# source_B.net
KiCad netlist of a schematic drawn in Altium Designer
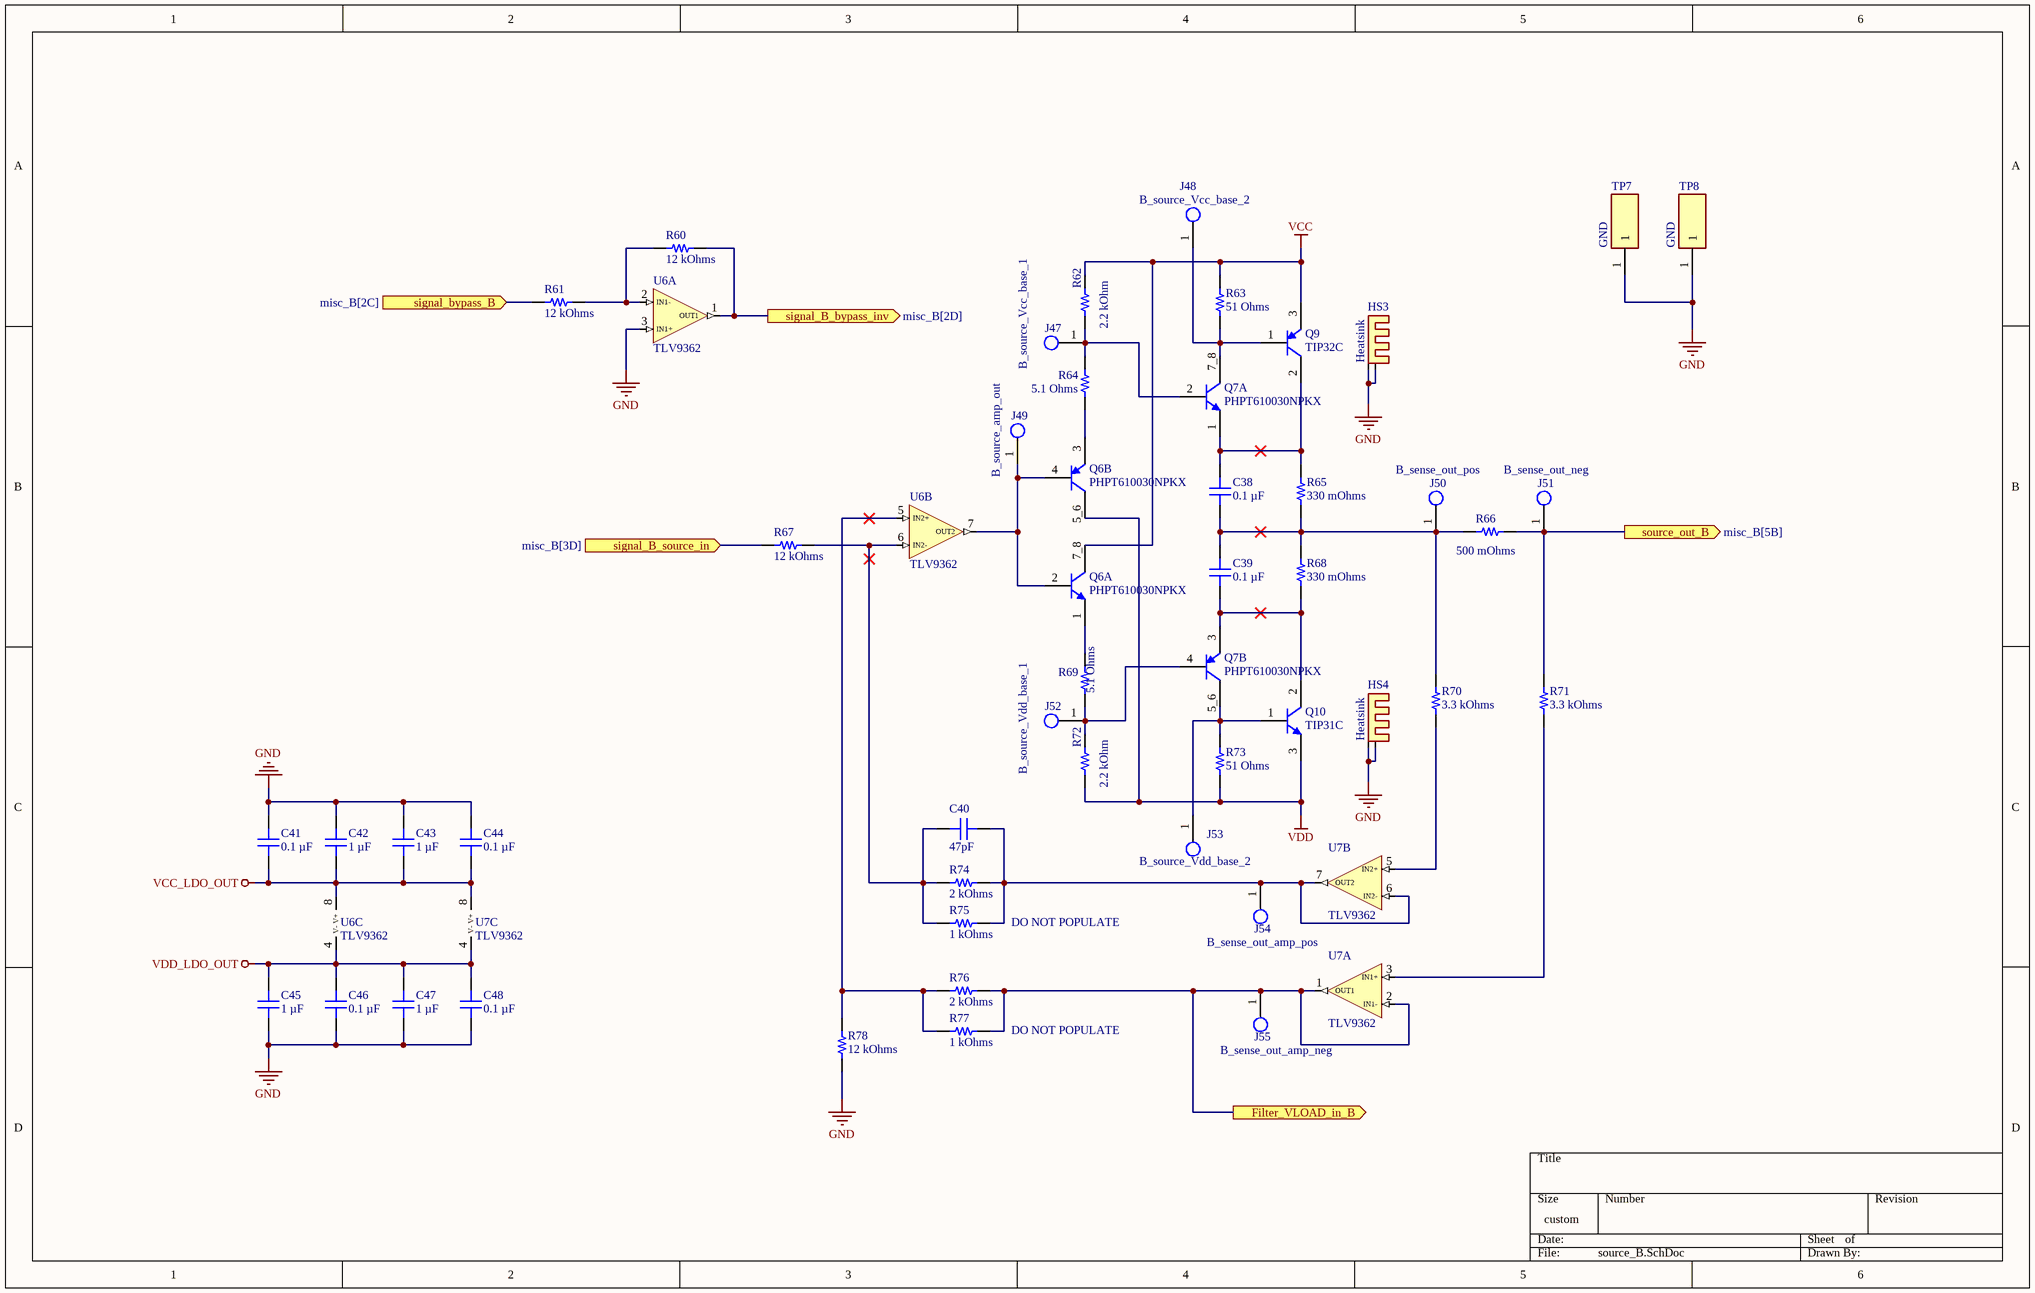
[diagram p0: source_B.SchDoc]

(export (version "E")
  (design (tool "Eeschema 10.0.6"))
  (components
    (comp (ref "C38")
      (value "0.1 µF")
      (footprint "CAP 1206_3216 - 0.8MM")
      (description "CAP CER 0.1UF 50V X7R 1206")
      (fields
        (field (name "PART NUMBER") "885012208087")
        (field (name "CAPACITANCE") "0.1 µF")
        (field (name "MANUFACTURER") "Würth Elektronik")
      )
      (libsource (lib "Celestial Altium Library - altium_library") (part "Capacitor"))
    )
    (comp (ref "C39")
      (value "0.1 µF")
      (footprint "CAP 1206_3216 - 0.8MM")
      (description "CAP CER 0.1UF 50V X7R 1206")
      (fields
        (field (name "PART NUMBER") "885012208087")
        (field (name "CAPACITANCE") "0.1 µF")
        (field (name "MANUFACTURER") "Würth Elektronik")
      )
      (libsource (lib "Celestial Altium Library - altium_library") (part "Capacitor"))
    )
    (comp (ref "C40")
      (value "47pF")
      (footprint "CAP 1206_3216 - 1.8MM")
      (description "CAP CER 47PF 1KV C0G/NP0 1206")
      (fields
        (field (name "PART NUMBER") "1206AA470KAT1A")
        (field (name "CAPACITANCE") "47pF")
        (field (name "MANUFACTURER") "AVX Corporation")
      )
      (libsource (lib "Celestial Altium Library - altium_library") (part "Capacitor"))
    )
    (comp (ref "C41")
      (value "0.1 µF")
      (footprint "CAP 1206_3216 - 0.8MM")
      (description "CAP CER 0.1UF 50V X7R 1206")
      (fields
        (field (name "PART NUMBER") "885012208087")
        (field (name "CAPACITANCE") "0.1 µF")
        (field (name "MANUFACTURER") "Würth Elektronik")
      )
      (libsource (lib "Celestial Altium Library - altium_library") (part "Capacitor"))
    )
    (comp (ref "C42")
      (value "1 µF")
      (footprint "CAP 1206_3216 - 0.8MM")
      (description "CAP CER 1UF 50V X7R 1206")
      (fields
        (field (name "PART NUMBER") "885012208093")
        (field (name "CAPACITANCE") "1 µF")
        (field (name "MANUFACTURER") "Würth Elektronik")
      )
      (libsource (lib "Celestial Altium Library - altium_library") (part "Capacitor"))
    )
    (comp (ref "C43")
      (value "1 µF")
      (footprint "CAP 1206_3216 - 0.8MM")
      (description "CAP CER 1UF 50V X7R 1206")
      (fields
        (field (name "PART NUMBER") "885012208093")
        (field (name "CAPACITANCE") "1 µF")
        (field (name "MANUFACTURER") "Würth Elektronik")
      )
      (libsource (lib "Celestial Altium Library - altium_library") (part "Capacitor"))
    )
    (comp (ref "C44")
      (value "0.1 µF")
      (footprint "CAP 1206_3216 - 0.8MM")
      (description "CAP CER 0.1UF 50V X7R 1206")
      (fields
        (field (name "PART NUMBER") "885012208087")
        (field (name "CAPACITANCE") "0.1 µF")
        (field (name "MANUFACTURER") "Würth Elektronik")
      )
      (libsource (lib "Celestial Altium Library - altium_library") (part "Capacitor"))
    )
    (comp (ref "C45")
      (value "1 µF")
      (footprint "CAP 1206_3216 - 0.8MM")
      (description "CAP CER 1UF 50V X7R 1206")
      (fields
        (field (name "PART NUMBER") "885012208093")
        (field (name "CAPACITANCE") "1 µF")
        (field (name "MANUFACTURER") "Würth Elektronik")
      )
      (libsource (lib "Celestial Altium Library - altium_library") (part "Capacitor"))
    )
    (comp (ref "C46")
      (value "0.1 µF")
      (footprint "CAP 1206_3216 - 0.8MM")
      (description "CAP CER 0.1UF 50V X7R 1206")
      (fields
        (field (name "PART NUMBER") "885012208087")
        (field (name "CAPACITANCE") "0.1 µF")
        (field (name "MANUFACTURER") "Würth Elektronik")
      )
      (libsource (lib "Celestial Altium Library - altium_library") (part "Capacitor"))
    )
    (comp (ref "C47")
      (value "1 µF")
      (footprint "CAP 1206_3216 - 0.8MM")
      (description "CAP CER 1UF 50V X7R 1206")
      (fields
        (field (name "PART NUMBER") "885012208093")
        (field (name "CAPACITANCE") "1 µF")
        (field (name "MANUFACTURER") "Würth Elektronik")
      )
      (libsource (lib "Celestial Altium Library - altium_library") (part "Capacitor"))
    )
    (comp (ref "C48")
      (value "0.1 µF")
      (footprint "CAP 1206_3216 - 0.8MM")
      (description "CAP CER 0.1UF 50V X7R 1206")
      (fields
        (field (name "PART NUMBER") "885012208087")
        (field (name "CAPACITANCE") "0.1 µF")
        (field (name "MANUFACTURER") "Würth Elektronik")
      )
      (libsource (lib "Celestial Altium Library - altium_library") (part "Capacitor"))
    )
    (comp (ref "HS3")
      (value "Heatsink")
      (footprint "593002B03400G")
      (description "593002B03400G Heatsink TO220 13.4 C/W")
      (fields
        (field (name "MANUFACTURER_PART_NUMBER") "593002B03400G")
        (field (name "MOUSER PART NUMBER") "532-593002B03400G")
      )
      (libsource (lib "za_koncar") (part "593002B03400G"))
    )
    (comp (ref "HS4")
      (value "Heatsink")
      (footprint "593002B03400G")
      (description "593002B03400G Heatsink TO220 13.4 C/W")
      (fields
        (field (name "MANUFACTURER_PART_NUMBER") "593002B03400G")
        (field (name "MOUSER PART NUMBER") "532-593002B03400G")
      )
      (libsource (lib "za_koncar") (part "593002B03400G"))
    )
    (comp (ref "J47")
      (value "B_source_Vcc_base_1")
      (footprint "FP-5001-MFG")
      (description "PC TEST POINT MINIATURE BLACK")
      (libsource (lib "za_koncar") (part "5001"))
    )
    (comp (ref "J48")
      (value "B_source_Vcc_base_2")
      (footprint "FP-5001-MFG")
      (description "PC TEST POINT MINIATURE BLACK")
      (libsource (lib "za_koncar") (part "5001"))
    )
    (comp (ref "J49")
      (value "B_source_amp_out")
      (footprint "FP-5001-MFG")
      (description "PC TEST POINT MINIATURE BLACK")
      (libsource (lib "za_koncar") (part "5001"))
    )
    (comp (ref "J50")
      (value "B_sense_out_pos")
      (footprint "FP-5001-MFG")
      (description "PC TEST POINT MINIATURE BLACK")
      (libsource (lib "za_koncar") (part "5001"))
    )
    (comp (ref "J51")
      (value "B_sense_out_neg")
      (footprint "FP-5001-MFG")
      (description "PC TEST POINT MINIATURE BLACK")
      (libsource (lib "za_koncar") (part "5001"))
    )
    (comp (ref "J52")
      (value "B_source_Vdd_base_1")
      (footprint "FP-5001-MFG")
      (description "PC TEST POINT MINIATURE BLACK")
      (libsource (lib "za_koncar") (part "5001"))
    )
    (comp (ref "J53")
      (value "B_source_Vdd_base_2")
      (footprint "FP-5001-MFG")
      (description "PC TEST POINT MINIATURE BLACK")
      (libsource (lib "za_koncar") (part "5001"))
    )
    (comp (ref "J54")
      (value "B_sense_out_amp_pos")
      (footprint "FP-5001-MFG")
      (description "PC TEST POINT MINIATURE BLACK")
      (libsource (lib "za_koncar") (part "5001"))
    )
    (comp (ref "J55")
      (value "B_sense_out_amp_neg")
      (footprint "FP-5001-MFG")
      (description "PC TEST POINT MINIATURE BLACK")
      (libsource (lib "za_koncar") (part "5001"))
    )
    (comp (ref "Q6")
      (value "PHPT610030NPKX")
      (footprint "TRANS_BUK9K18-40E,115")
      (libsource (lib "za_koncar") (part "PHPT610030NPKX"))
    )
    (comp (ref "Q7")
      (value "PHPT610030NPKX")
      (footprint "TRANS_BUK9K18-40E,115")
      (libsource (lib "za_koncar") (part "PHPT610030NPKX"))
    )
    (comp (ref "Q9")
      (value "TIP32C")
      (footprint "ONSC-TO-220-3-221A-09")
      (description "Complementary Silicon Plastic Power Transistor, 3-Pin TO-220, Tube")
      (fields (field (name "MANUFACTURER") "On Semiconductor"))
      (libsource (lib "ON Semi General Purpose Transistors") (part "TIP32C"))
    )
    (comp (ref "Q10")
      (value "TIP31C")
      (footprint "ONSC-TO-220-3-221A-09")
      (description "Complementary Silicon Plastic Power Transistor, 3-Pin TO-220, Tube")
      (fields (field (name "MANUFACTURER") "On Semiconductor"))
      (libsource (lib "ON Semi General Purpose Transistors") (part "TIP31C"))
    )
    (comp (ref "R60")
      (value "12 kOhms")
      (footprint "RES 1206_3216")
      (description "RES SMD 12K OHM 0.1% 1/4W 1206")
      (fields
        (field (name "PART NUMBER") "ERA-8AEB123V")
        (field (name "MANUFACTURER") "Panasonic Electronic Components")
      )
      (libsource (lib "Celestial Altium Library - altium_library") (part "Resistor"))
    )
    (comp (ref "R61")
      (value "12 kOhms")
      (footprint "RES 1206_3216")
      (description "RES SMD 12K OHM 0.1% 1/4W 1206")
      (fields
        (field (name "PART NUMBER") "ERA-8AEB123V")
        (field (name "MANUFACTURER") "Panasonic Electronic Components")
      )
      (libsource (lib "Celestial Altium Library - altium_library") (part "Resistor"))
    )
    (comp (ref "R62")
      (value "2.2 kOhm")
      (footprint "za_koncar:RESC3116X65N")
      (description "Resistor")
      (fields
        (field (name "MANUFACTURER_PART_NUMBER") "RT1206FRE072K2L")
        (field (name "MOUSER PART NUMBER") "603-RT1206FRE072K2L")
      )
      (libsource (lib "za_koncar") (part "RT1206FRE072K2L"))
    )
    (comp (ref "R63")
      (value "51 Ohms")
      (footprint "RES 1206_3216")
      (description "RES SMD 51 OHM 5% 1/4W 1206")
      (fields
        (field (name "PART NUMBER") "ERJ-8GEYJ510V")
        (field (name "MANUFACTURER") "Panasonic Electronic Components")
      )
      (libsource (lib "Celestial Altium Library - altium_library") (part "Resistor"))
    )
    (comp (ref "R64")
      (value "5.1 Ohms")
      (footprint "RES 1206_3216")
      (description "RES SMD 5.1 OHM 5% 1/4W 1206")
      (fields
        (field (name "PART NUMBER") "ERJ-8GEYJ5R1V")
        (field (name "MANUFACTURER") "Panasonic Electronic Components")
      )
      (libsource (lib "Celestial Altium Library - altium_library") (part "Resistor"))
    )
    (comp (ref "R65")
      (value "330 mOhms")
      (footprint "STACKPOLE CSR2512")
      (description "RES 0.33 OHM 1% 2W 2512")
      (fields
        (field (name "PART NUMBER") "CSRN2512FKR330")
        (field (name "MANUFACTURER") "Stackpole Electronics Inc")
      )
      (libsource (lib "Celestial Altium Library - altium_library") (part "Resistor"))
    )
    (comp (ref "R66")
      (value "500 mOhms")
      (footprint "STACKPOLE CSR2512")
      (description "RES 0.5 OHM 1% 2W 2512")
      (fields
        (field (name "PART NUMBER") "CSRN2512FKR500")
        (field (name "MANUFACTURER") "Stackpole Electronics Inc")
      )
      (libsource (lib "Celestial Altium Library - altium_library") (part "Resistor"))
    )
    (comp (ref "R67")
      (value "12 kOhms")
      (footprint "RES 1206_3216")
      (description "RES SMD 12K OHM 0.1% 1/4W 1206")
      (fields
        (field (name "PART NUMBER") "ERA-8AEB123V")
        (field (name "MANUFACTURER") "Panasonic Electronic Components")
      )
      (libsource (lib "Celestial Altium Library - altium_library") (part "Resistor"))
    )
    (comp (ref "R68")
      (value "330 mOhms")
      (footprint "STACKPOLE CSR2512")
      (description "RES 0.33 OHM 1% 2W 2512")
      (fields
        (field (name "PART NUMBER") "CSRN2512FKR330")
        (field (name "MANUFACTURER") "Stackpole Electronics Inc")
      )
      (libsource (lib "Celestial Altium Library - altium_library") (part "Resistor"))
    )
    (comp (ref "R69")
      (value "5.1 Ohms")
      (footprint "RES 1206_3216")
      (description "RES SMD 5.1 OHM 5% 1/4W 1206")
      (fields
        (field (name "PART NUMBER") "ERJ-8GEYJ5R1V")
        (field (name "MANUFACTURER") "Panasonic Electronic Components")
      )
      (libsource (lib "Celestial Altium Library - altium_library") (part "Resistor"))
    )
    (comp (ref "R70")
      (value "3.3 kOhms")
      (footprint "YAGEO RES 1206_3216")
      (description "RES SMD 3.3K OHM 1% 1/4W 1206")
      (fields (field (name "PART NUMBER") "RT1206FRE073K3L") (field (name "MANUFACTURER") "Yageo"))
      (libsource (lib "Celestial Altium Library - altium_library") (part "Resistor"))
    )
    (comp (ref "R71")
      (value "3.3 kOhms")
      (footprint "YAGEO RES 1206_3216")
      (description "RES SMD 3.3K OHM 1% 1/4W 1206")
      (fields (field (name "PART NUMBER") "RT1206FRE073K3L") (field (name "MANUFACTURER") "Yageo"))
      (libsource (lib "Celestial Altium Library - altium_library") (part "Resistor"))
    )
    (comp (ref "R72")
      (value "2.2 kOhm")
      (footprint "za_koncar:RESC3116X65N")
      (description "Resistor")
      (fields
        (field (name "MANUFACTURER_PART_NUMBER") "RT1206FRE072K2L")
        (field (name "MOUSER PART NUMBER") "603-RT1206FRE072K2L")
      )
      (libsource (lib "za_koncar") (part "RT1206FRE072K2L"))
    )
    (comp (ref "R73")
      (value "51 Ohms")
      (footprint "RES 1206_3216")
      (description "RES SMD 51 OHM 5% 1/4W 1206")
      (fields
        (field (name "PART NUMBER") "ERJ-8GEYJ510V")
        (field (name "MANUFACTURER") "Panasonic Electronic Components")
      )
      (libsource (lib "Celestial Altium Library - altium_library") (part "Resistor"))
    )
    (comp (ref "R74")
      (value "2 kOhms")
      (footprint "RES 1206_3216")
      (description "RES SMD 2K OHM 0.1% 1/4W 1206")
      (fields
        (field (name "PART NUMBER") "ERA-8AEB202V")
        (field (name "MANUFACTURER") "Panasonic Electronic Components")
      )
      (libsource (lib "Celestial Altium Library - altium_library") (part "Resistor"))
    )
    (comp (ref "R75")
      (value "1 kOhms")
      (footprint "RES 1206_3216")
      (description "RES SMD 1K OHM 0.1% 1/4W 1206")
      (fields
        (field (name "PART NUMBER") "ERA-8AEB102V")
        (field (name "MANUFACTURER") "Panasonic Electronic Components")
      )
      (libsource (lib "Celestial Altium Library - altium_library") (part "Resistor"))
    )
    (comp (ref "R76")
      (value "2 kOhms")
      (footprint "RES 1206_3216")
      (description "RES SMD 2K OHM 0.1% 1/4W 1206")
      (fields
        (field (name "PART NUMBER") "ERA-8AEB202V")
        (field (name "MANUFACTURER") "Panasonic Electronic Components")
      )
      (libsource (lib "Celestial Altium Library - altium_library") (part "Resistor"))
    )
    (comp (ref "R77")
      (value "1 kOhms")
      (footprint "RES 1206_3216")
      (description "RES SMD 1K OHM 0.1% 1/4W 1206")
      (fields
        (field (name "PART NUMBER") "ERA-8AEB102V")
        (field (name "MANUFACTURER") "Panasonic Electronic Components")
      )
      (libsource (lib "Celestial Altium Library - altium_library") (part "Resistor"))
    )
    (comp (ref "R78")
      (value "12 kOhms")
      (footprint "RES 1206_3216")
      (description "RES SMD 12K OHM 0.1% 1/4W 1206")
      (fields
        (field (name "PART NUMBER") "ERA-8AEB123V")
        (field (name "MANUFACTURER") "Panasonic Electronic Components")
      )
      (libsource (lib "Celestial Altium Library - altium_library") (part "Resistor"))
    )
    (comp (ref "TP7")
      (value "GND")
      (footprint "za_koncar:S175146R")
      (description "Test Point")
      (fields
        (field (name "MANUFACTURER_PART_NUMBER") "S1751-46R")
        (field (name "MOUSER PART NUMBER") "855-S1751-46R")
      )
      (libsource (lib "za_koncar") (part "S1751-46R"))
    )
    (comp (ref "TP8")
      (value "GND")
      (footprint "za_koncar:S175146R")
      (description "Test Point")
      (fields
        (field (name "MANUFACTURER_PART_NUMBER") "S1751-46R")
        (field (name "MOUSER PART NUMBER") "855-S1751-46R")
      )
      (libsource (lib "za_koncar") (part "S1751-46R"))
    )
    (comp (ref "U6")
      (value "TLV9362")
      (footprint "SOIC8-127P600X175-8N")
      (description "TLV936x 10-MHz, 40-V, RRO, Operational Amplifie")
      (libsource (lib "za_koncar") (part "TLV9362"))
    )
    (comp (ref "U7")
      (value "TLV9362")
      (footprint "SOIC8-127P600X175-8N")
      (description "TLV936x 10-MHz, 40-V, RRO, Operational Amplifie")
      (libsource (lib "za_koncar") (part "TLV9362"))
    )
  )
  (nets
    (net (code "1") (name "/Filter_VLOAD_in_B") (class "Default")
      (node (ref "J55") (pin "1") (pinfunction "1_1") (pintype "passive"))
      (node (ref "R76") (pin "2") (pinfunction "2_2") (pintype "passive"))
      (node (ref "R77") (pin "2") (pinfunction "2_2") (pintype "passive"))
      (node (ref "U7") (pin "1") (pinfunction "OUT1_1") (pintype "output"))
      (node (ref "U7") (pin "2") (pinfunction "IN1-_2") (pintype "input"))
    )
    (net (code "2") (name "/signal_B_bypass_inv") (class "Default")
      (node (ref "R60") (pin "2") (pinfunction "2_2") (pintype "passive"))
      (node (ref "U6") (pin "1") (pinfunction "OUT1_1") (pintype "output"))
    )
    (net (code "3") (name "/signal_B_source_in") (class "Default")
      (node (ref "R67") (pin "2") (pinfunction "2_2") (pintype "passive"))
    )
    (net (code "4") (name "/signal_bypass_B") (class "Default")
      (node (ref "R61") (pin "2") (pinfunction "2_2") (pintype "passive"))
    )
    (net (code "5") (name "/source_out_B") (class "Default")
      (node (ref "J51") (pin "1") (pinfunction "1_1") (pintype "passive"))
      (node (ref "R66") (pin "1") (pinfunction "1_1") (pintype "passive"))
      (node (ref "R71") (pin "1") (pinfunction "1_1") (pintype "passive"))
    )
    (net (code "6") (name "GND") (class "Default")
      (node (ref "C41") (pin "1") (pinfunction "1_1") (pintype "passive"))
      (node (ref "C42") (pin "1") (pinfunction "1_1") (pintype "passive"))
      (node (ref "C43") (pin "2") (pinfunction "2_2") (pintype "passive"))
      (node (ref "C44") (pin "2") (pinfunction "2_2") (pintype "passive"))
      (node (ref "C45") (pin "2") (pinfunction "2_2") (pintype "passive"))
      (node (ref "C46") (pin "2") (pinfunction "2_2") (pintype "passive"))
      (node (ref "C47") (pin "2") (pinfunction "2_2") (pintype "passive"))
      (node (ref "C48") (pin "2") (pinfunction "2_2") (pintype "passive"))
      (node (ref "HS3") (pin "1") (pinfunction "1_1") (pintype "passive"))
      (node (ref "HS3") (pin "2") (pinfunction "2_2") (pintype "passive"))
      (node (ref "HS4") (pin "1") (pinfunction "1_1") (pintype "passive"))
      (node (ref "HS4") (pin "2") (pinfunction "2_2") (pintype "passive"))
      (node (ref "R78") (pin "1") (pinfunction "1_1") (pintype "passive"))
      (node (ref "TP7") (pin "1") (pinfunction "1_1") (pintype "passive"))
      (node (ref "TP8") (pin "1") (pinfunction "1_1") (pintype "passive"))
      (node (ref "U6") (pin "3") (pinfunction "IN1+_3") (pintype "input"))
    )
    (net (code "7") (name "Net-(C38-Pad1)") (class "Default")
      (node (ref "C38") (pin "1") (pinfunction "1_1") (pintype "passive"))
      (node (ref "C39") (pin "2") (pinfunction "2_2") (pintype "passive"))
      (node (ref "J50") (pin "1") (pinfunction "1_1") (pintype "passive"))
      (node (ref "R65") (pin "1") (pinfunction "1_1") (pintype "passive"))
      (node (ref "R66") (pin "2") (pinfunction "2_2") (pintype "passive"))
      (node (ref "R68") (pin "2") (pinfunction "2_2") (pintype "passive"))
      (node (ref "R70") (pin "1") (pinfunction "1_1") (pintype "passive"))
    )
    (net (code "8") (name "Net-(Q6A-B1)") (class "Default")
      (node (ref "J49") (pin "1") (pinfunction "1_1") (pintype "passive"))
      (node (ref "Q6") (pin "2") (pinfunction "B1_2") (pintype "passive"))
      (node (ref "Q6") (pin "4") (pinfunction "B2_4") (pintype "passive"))
      (node (ref "U6") (pin "7") (pinfunction "OUT2_7") (pintype "output"))
    )
    (net (code "9") (name "Net-(Q6A-E1)") (class "Default")
      (node (ref "Q6") (pin "1") (pinfunction "E1_1") (pintype "passive"))
      (node (ref "R69") (pin "2") (pinfunction "2_2") (pintype "passive"))
    )
    (net (code "10") (name "Net-(Q6B-E2)") (class "Default")
      (node (ref "Q6") (pin "3") (pinfunction "E2_3") (pintype "passive"))
      (node (ref "R64") (pin "1") (pinfunction "1_1") (pintype "passive"))
    )
    (net (code "11") (name "Net-(Q7A-B1)") (class "Default")
      (node (ref "J47") (pin "1") (pinfunction "1_1") (pintype "passive"))
      (node (ref "Q7") (pin "2") (pinfunction "B1_2") (pintype "passive"))
      (node (ref "R62") (pin "1") (pinfunction "1_1") (pintype "passive"))
      (node (ref "R64") (pin "2") (pinfunction "2_2") (pintype "passive"))
    )
    (net (code "12") (name "Net-(Q7A-C1)") (class "Default")
      (node (ref "J48") (pin "1") (pinfunction "1_1") (pintype "passive"))
      (node (ref "Q7") (pin "7_8") (pinfunction "C1_7_8") (pintype "passive"))
      (node (ref "Q9") (pin "1") (pinfunction "B_1") (pintype "passive"))
      (node (ref "R63") (pin "1") (pinfunction "1_1") (pintype "passive"))
    )
    (net (code "13") (name "Net-(Q7A-E1)") (class "Default")
      (node (ref "C38") (pin "2") (pinfunction "2_2") (pintype "passive"))
      (node (ref "Q7") (pin "1") (pinfunction "E1_1") (pintype "passive"))
      (node (ref "Q9") (pin "2") (pinfunction "C_2") (pintype "passive"))
      (node (ref "R65") (pin "2") (pinfunction "2_2") (pintype "passive"))
    )
    (net (code "14") (name "Net-(Q7B-B2)") (class "Default")
      (node (ref "J52") (pin "1") (pinfunction "1_1") (pintype "passive"))
      (node (ref "Q7") (pin "4") (pinfunction "B2_4") (pintype "passive"))
      (node (ref "R69") (pin "1") (pinfunction "1_1") (pintype "passive"))
      (node (ref "R72") (pin "2") (pinfunction "2_2") (pintype "passive"))
    )
    (net (code "15") (name "Net-(Q10-B)") (class "Default")
      (node (ref "J53") (pin "1") (pinfunction "1_1") (pintype "passive"))
      (node (ref "Q10") (pin "1") (pinfunction "B_1") (pintype "passive"))
      (node (ref "Q7") (pin "5_6") (pinfunction "C2_5_6") (pintype "passive"))
      (node (ref "R73") (pin "2") (pinfunction "2_2") (pintype "passive"))
    )
    (net (code "16") (name "Net-(Q10-C)") (class "Default")
      (node (ref "C39") (pin "1") (pinfunction "1_1") (pintype "passive"))
      (node (ref "Q10") (pin "2") (pinfunction "C_2") (pintype "passive"))
      (node (ref "Q7") (pin "3") (pinfunction "E2_3") (pintype "passive"))
      (node (ref "R68") (pin "1") (pinfunction "1_1") (pintype "passive"))
    )
    (net (code "17") (name "Net-(U6A-IN1-)") (class "Default")
      (node (ref "R60") (pin "1") (pinfunction "1_1") (pintype "passive"))
      (node (ref "R61") (pin "1") (pinfunction "1_1") (pintype "passive"))
      (node (ref "U6") (pin "2") (pinfunction "IN1-_2") (pintype "input"))
    )
    (net (code "18") (name "Net-(U6B-IN2+)") (class "Default")
      (node (ref "R76") (pin "1") (pinfunction "1_1") (pintype "passive"))
      (node (ref "R77") (pin "1") (pinfunction "1_1") (pintype "passive"))
      (node (ref "R78") (pin "2") (pinfunction "2_2") (pintype "passive"))
      (node (ref "U6") (pin "5") (pinfunction "IN2+_5") (pintype "input"))
    )
    (net (code "19") (name "Net-(U6B-IN2-)") (class "Default")
      (node (ref "C40") (pin "1") (pinfunction "1_1") (pintype "passive"))
      (node (ref "R67") (pin "1") (pinfunction "1_1") (pintype "passive"))
      (node (ref "R74") (pin "1") (pinfunction "1_1") (pintype "passive"))
      (node (ref "R75") (pin "1") (pinfunction "1_1") (pintype "passive"))
      (node (ref "U6") (pin "6") (pinfunction "IN2-_6") (pintype "input"))
    )
    (net (code "20") (name "Net-(U7A-IN1+)") (class "Default")
      (node (ref "R71") (pin "2") (pinfunction "2_2") (pintype "passive"))
      (node (ref "U7") (pin "3") (pinfunction "IN1+_3") (pintype "input"))
    )
    (net (code "21") (name "Net-(U7B-IN2+)") (class "Default")
      (node (ref "R70") (pin "2") (pinfunction "2_2") (pintype "passive"))
      (node (ref "U7") (pin "5") (pinfunction "IN2+_5") (pintype "input"))
    )
    (net (code "22") (name "Net-(U7B-IN2-)") (class "Default")
      (node (ref "C40") (pin "2") (pinfunction "2_2") (pintype "passive"))
      (node (ref "J54") (pin "1") (pinfunction "1_1") (pintype "passive"))
      (node (ref "R74") (pin "2") (pinfunction "2_2") (pintype "passive"))
      (node (ref "R75") (pin "2") (pinfunction "2_2") (pintype "passive"))
      (node (ref "U7") (pin "6") (pinfunction "IN2-_6") (pintype "input"))
      (node (ref "U7") (pin "7") (pinfunction "OUT2_7") (pintype "output"))
    )
    (net (code "23") (name "VCC") (class "Default")
      (node (ref "Q6") (pin "7_8") (pinfunction "C1_7_8") (pintype "passive"))
      (node (ref "Q9") (pin "3") (pinfunction "E_3") (pintype "passive"))
      (node (ref "R62") (pin "2") (pinfunction "2_2") (pintype "passive"))
      (node (ref "R63") (pin "2") (pinfunction "2_2") (pintype "passive"))
    )
    (net (code "24") (name "VCC_LDO_OUT") (class "Default")
      (node (ref "C41") (pin "2") (pinfunction "2_2") (pintype "passive"))
      (node (ref "C42") (pin "2") (pinfunction "2_2") (pintype "passive"))
      (node (ref "C43") (pin "1") (pinfunction "1_1") (pintype "passive"))
      (node (ref "C44") (pin "1") (pinfunction "1_1") (pintype "passive"))
      (node (ref "U6") (pin "8") (pinfunction "V+_8") (pintype "power_in"))
      (node (ref "U7") (pin "8") (pinfunction "V+_8") (pintype "power_in"))
    )
    (net (code "25") (name "VDD") (class "Default")
      (node (ref "Q10") (pin "3") (pinfunction "E_3") (pintype "passive"))
      (node (ref "Q6") (pin "5_6") (pinfunction "C2_5_6") (pintype "passive"))
      (node (ref "R72") (pin "1") (pinfunction "1_1") (pintype "passive"))
      (node (ref "R73") (pin "1") (pinfunction "1_1") (pintype "passive"))
    )
    (net (code "26") (name "VDD_LDO_OUT") (class "Default")
      (node (ref "C45") (pin "1") (pinfunction "1_1") (pintype "passive"))
      (node (ref "C46") (pin "1") (pinfunction "1_1") (pintype "passive"))
      (node (ref "C47") (pin "1") (pinfunction "1_1") (pintype "passive"))
      (node (ref "C48") (pin "1") (pinfunction "1_1") (pintype "passive"))
      (node (ref "U6") (pin "4") (pinfunction "V-_4") (pintype "power_in"))
      (node (ref "U7") (pin "4") (pinfunction "V-_4") (pintype "power_in"))
    )
  )
)
